# deel2.net
KiCad netlist of a schematic drawn in Altium Designer
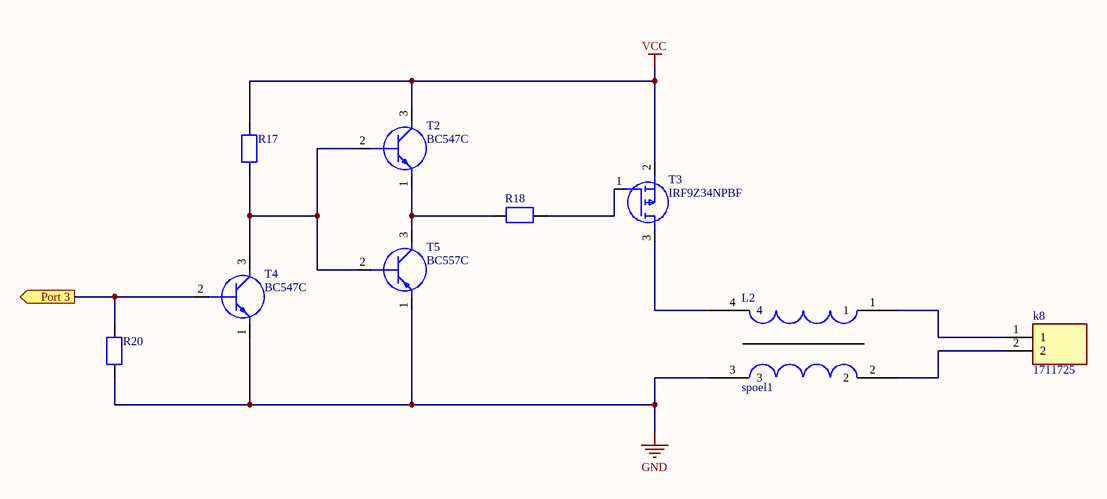
[diagram p0: deel2_....SchDoc]

(export (version "E")
  (design (tool "Eeschema 10.0.6"))
  (components
    (comp (ref "k8")
      (value "1711725")
      (footprint "1711725")
      (description "Connector")
      (fields (field (name "MOUSER PART NUMBER") "651-1711725"))
      (libsource (lib "SoldeerboutLib") (part "1711725"))
    )
    (comp (ref "L2")
      (value "spoel1")
      (footprint "CM2545X171B10")
      (libsource (lib "SoldeerboutLib") (part "spoel1"))
    )
    (comp (ref "R17")
      (value "CRCW08050000Z0EA")
      (footprint "RESC2013X50X30LL20T20")
      (description "4k7")
      (fields (field (name "MANUFACTURER") "Vishay Dale"))
      (libsource (lib "SoldeerboutLib") (part "resistor"))
    )
    (comp (ref "R18")
      (value "CRCW08050000Z0EA")
      (footprint "RESC2013X50X30LL20T20")
      (description "100Ohm")
      (fields (field (name "MANUFACTURER") "Vishay Dale"))
      (libsource (lib "SoldeerboutLib") (part "resistor"))
    )
    (comp (ref "R20")
      (value "CRCW08050000Z0EA")
      (footprint "RESC2013X50X30LL20T20")
      (description "4k7")
      (fields (field (name "MANUFACTURER") "Vishay Dale"))
      (libsource (lib "SoldeerboutLib") (part "resistor"))
    )
    (comp (ref "T2")
      (value "BC547C")
      (footprint "SamacSys:BC547C")
      (description "Transistor BJT NPN")
      (fields (field (name "MOUSER PART NUMBER") "771-BC547C"))
      (libsource (lib "SoldeerboutLib") (part "BC547C"))
    )
    (comp (ref "T3")
      (value "IRF9Z34NPBF")
      (footprint "SamacSys:TO254P469X1042X1967-3P")
      (description "MOSFET (P-Channel)")
      (fields (field (name "MOUSER PART NUMBER") "942-IRF9Z34NPBF"))
      (libsource (lib "SoldeerboutLib") (part "IRF9Z34NPBF"))
    )
    (comp (ref "T4")
      (value "BC547C")
      (footprint "SamacSys:BC547C")
      (description "Transistor BJT NPN")
      (fields (field (name "MOUSER PART NUMBER") "771-BC547C"))
      (libsource (lib "SoldeerboutLib") (part "BC547C"))
    )
    (comp (ref "T5")
      (value "BC557C")
      (footprint "SamacSys:BC557C")
      (description "Transistor BJT PNP")
      (fields (field (name "MOUSER PART NUMBER") "771-BC557C"))
      (libsource (lib "SoldeerboutLib") (part "BC557C"))
    )
  )
  (nets
    (net (code "1") (name "/Port 3") (class "Default")
      (node (ref "R20") (pin "2") (pinfunction "2_2") (pintype "passive"))
      (node (ref "T4") (pin "2") (pinfunction "B_2") (pintype "passive"))
    )
    (net (code "2") (name "GND") (class "Default")
      (node (ref "L2") (pin "3") (pinfunction "3_3") (pintype "passive"))
      (node (ref "R20") (pin "1") (pinfunction "1_1") (pintype "passive"))
      (node (ref "T4") (pin "1") (pinfunction "E_1") (pintype "passive"))
      (node (ref "T5") (pin "1") (pinfunction "E_1") (pintype "passive"))
    )
    (net (code "3") (name "Net-(L2-Pad1)") (class "Default")
      (node (ref "L2") (pin "1") (pinfunction "1_1") (pintype "passive"))
      (node (ref "k8") (pin "1") (pinfunction "1_1") (pintype "passive"))
    )
    (net (code "4") (name "Net-(L2-Pad2)") (class "Default")
      (node (ref "L2") (pin "2") (pinfunction "2_2") (pintype "passive"))
      (node (ref "k8") (pin "2") (pinfunction "2_2") (pintype "passive"))
    )
    (net (code "5") (name "Net-(T2-B)") (class "Default")
      (node (ref "R17") (pin "1") (pinfunction "1_1") (pintype "passive"))
      (node (ref "T2") (pin "2") (pinfunction "B_2") (pintype "passive"))
      (node (ref "T4") (pin "3") (pinfunction "C_3") (pintype "passive"))
      (node (ref "T5") (pin "2") (pinfunction "B_2") (pintype "passive"))
    )
    (net (code "6") (name "Net-(T2-E)") (class "Default")
      (node (ref "R18") (pin "1") (pinfunction "1_1") (pintype "passive"))
      (node (ref "T2") (pin "1") (pinfunction "E_1") (pintype "passive"))
      (node (ref "T5") (pin "3") (pinfunction "C_3") (pintype "passive"))
    )
    (net (code "7") (name "Net-(T3-D)") (class "Default")
      (node (ref "L2") (pin "4") (pinfunction "4_4") (pintype "passive"))
      (node (ref "T3") (pin "3") (pinfunction "D_3") (pintype "passive"))
    )
    (net (code "8") (name "Net-(T3-G)") (class "Default")
      (node (ref "R18") (pin "2") (pinfunction "2_2") (pintype "passive"))
      (node (ref "T3") (pin "1") (pinfunction "G_1") (pintype "passive"))
    )
    (net (code "9") (name "VCC") (class "Default")
      (node (ref "R17") (pin "2") (pinfunction "2_2") (pintype "passive"))
      (node (ref "T2") (pin "3") (pinfunction "C_3") (pintype "passive"))
      (node (ref "T3") (pin "2") (pinfunction "S_2") (pintype "passive"))
    )
  )
)
